# untitled.net
KiCad netlist of a schematic drawn in EAGLE
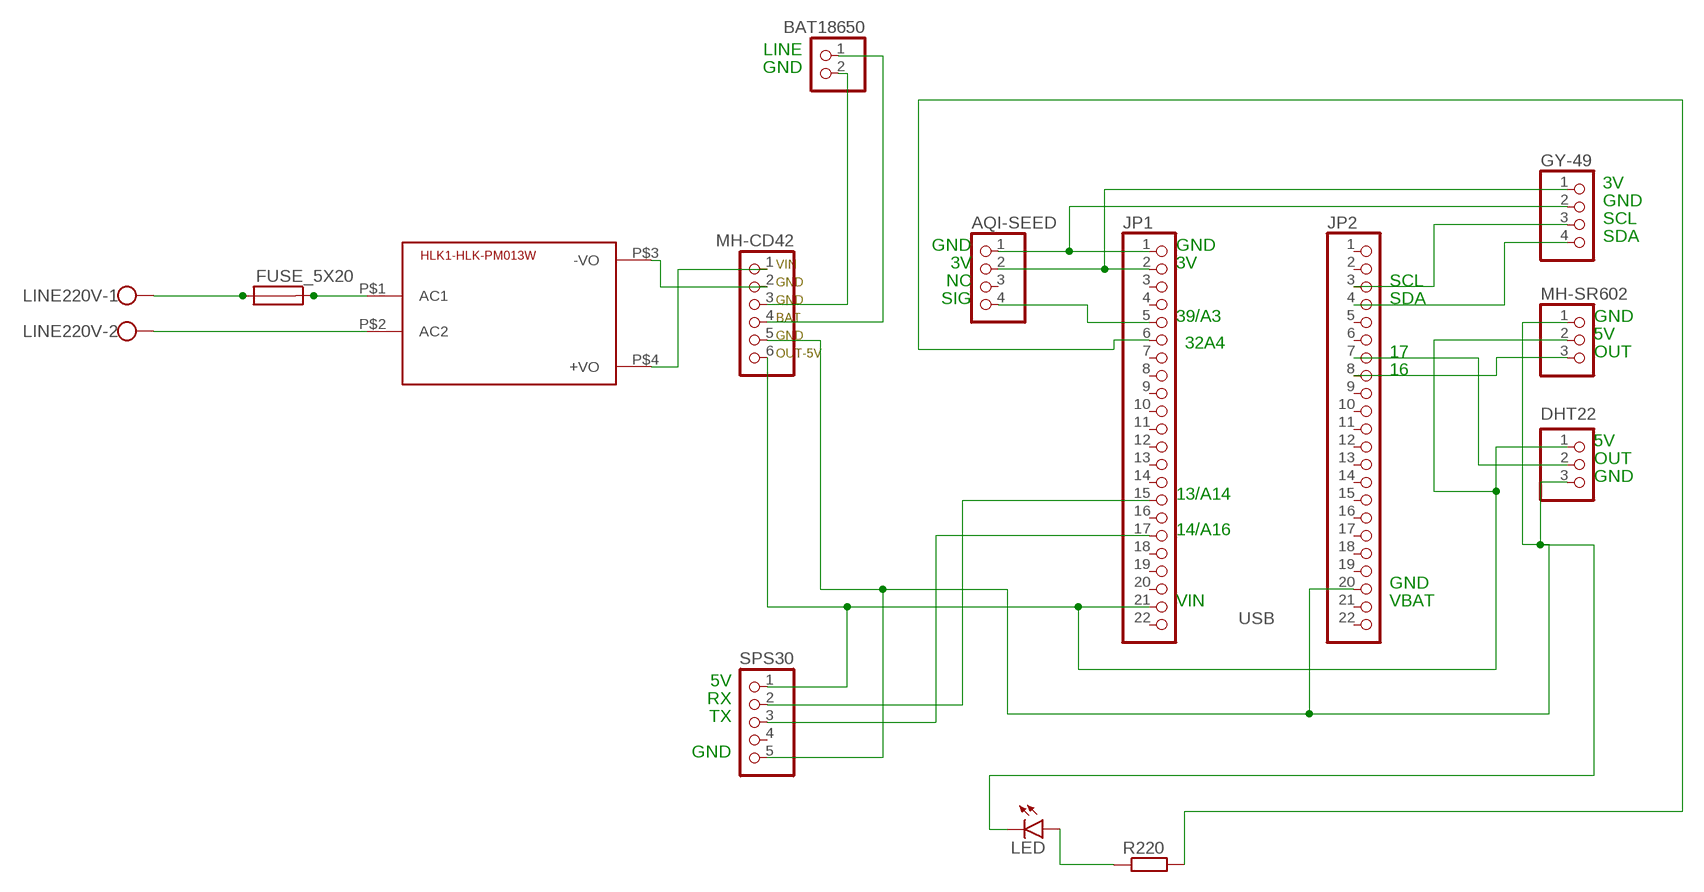
[diagram p0: schematic, sheet 1]

(export (version "E")
  (design (tool "Eeschema 10.0.6"))
  (components
    (comp (ref "AQI-SEED")
      (value "PINHD-1X4")
      (footprint "eagle-import:1X04")
      (libsource (lib "eagle-import") (part "PINHD-1X4"))
    )
    (comp (ref "BAT18650")
      (value "PINHD-1X2")
      (footprint "eagle-import:1X02")
      (libsource (lib "eagle-import") (part "PINHD-1X2"))
    )
    (comp (ref "FUSE_5X20")
      (value "FH_5X20")
      (footprint "eagle-import:FH_5X20")
      (libsource (lib "eagle-import") (part "FH_5X20"))
    )
    (comp (ref "GY-49")
      (value "PINHD-1X4")
      (footprint "eagle-import:1X04")
      (libsource (lib "eagle-import") (part "PINHD-1X4"))
    )
    (comp (ref "HLK1-HLK-PM013W")
      (value "HLK-PM013W")
      (footprint "eagle-import:HLK-PM01")
      (libsource (lib "eagle-import") (part "HLK-PM013W"))
    )
    (comp (ref "JP1")
      (value "PINHD-1X22")
      (footprint "eagle-import:1X22")
      (libsource (lib "eagle-import") (part "PINHD-1X22"))
    )
    (comp (ref "JP2")
      (value "PINHD-1X22")
      (footprint "eagle-import:1X22")
      (libsource (lib "eagle-import") (part "PINHD-1X22"))
    )
    (comp (ref "JP6")
      (value "DHT22")
      (footprint "eagle-import:1X03")
      (libsource (lib "eagle-import") (part "PINHD-1X3"))
    )
    (comp (ref "LED")
      (value "LED3MM")
      (footprint "eagle-import:LED3MM")
      (libsource (lib "eagle-import") (part "LED3MM"))
    )
    (comp (ref "LINE220V")
      (value "W237-102")
      (footprint "eagle-import:W237-102")
      (fields (field (name "MPN") "237-102"))
      (libsource (lib "eagle-import") (part "W237-102"))
    )
    (comp (ref "MH-CD42")
      (value "PINHD-1X6")
      (footprint "eagle-import:1X06")
      (fields (field (name "SPICEPREFIX") "X"))
      (libsource (lib "eagle-import") (part "PINHD-1X6"))
    )
    (comp (ref "MH-SR602")
      (value "PINHD-1X3")
      (footprint "eagle-import:1X03")
      (libsource (lib "eagle-import") (part "PINHD-1X3"))
    )
    (comp (ref "R220")
      (value "R-EU_0204/5")
      (footprint "eagle-import:0204_5")
      (libsource (lib "eagle-import") (part "R-EU_0204/5"))
    )
    (comp (ref "SPS30")
      (value "PINHD-1X5")
      (footprint "eagle-import:1X05")
      (libsource (lib "eagle-import") (part "PINHD-1X5"))
    )
  )
  (nets
    (net (code "1") (name "Net-(AQI-SEED-Pad1)") (class "Default")
      (node (ref "AQI-SEED") (pin "1") (pinfunction "1_1") (pintype "passive"))
      (node (ref "GY-49") (pin "2") (pinfunction "2_2") (pintype "passive"))
      (node (ref "JP1") (pin "1") (pinfunction "1_1") (pintype "passive"))
    )
    (net (code "2") (name "Net-(AQI-SEED-Pad2)") (class "Default")
      (node (ref "AQI-SEED") (pin "2") (pinfunction "2_2") (pintype "passive"))
      (node (ref "GY-49") (pin "1") (pinfunction "1_1") (pintype "passive"))
      (node (ref "JP1") (pin "2") (pinfunction "2_2") (pintype "passive"))
    )
    (net (code "3") (name "Net-(AQI-SEED-Pad4)") (class "Default")
      (node (ref "AQI-SEED") (pin "4") (pinfunction "4_4") (pintype "passive"))
      (node (ref "JP1") (pin "5") (pinfunction "5_5") (pintype "passive"))
    )
    (net (code "4") (name "Net-(BAT18650-Pad1)") (class "Default")
      (node (ref "BAT18650") (pin "1") (pinfunction "1_1") (pintype "passive"))
      (node (ref "MH-CD42") (pin "4") (pinfunction "4_4") (pintype "passive"))
    )
    (net (code "5") (name "Net-(BAT18650-Pad2)") (class "Default")
      (node (ref "BAT18650") (pin "2") (pinfunction "2_2") (pintype "passive"))
      (node (ref "MH-CD42") (pin "3") (pinfunction "3_3") (pintype "passive"))
    )
    (net (code "6") (name "Net-(GY-49-Pad3)") (class "Default")
      (node (ref "GY-49") (pin "3") (pinfunction "3_3") (pintype "passive"))
      (node (ref "JP2") (pin "3") (pinfunction "3_3") (pintype "passive"))
    )
    (net (code "7") (name "Net-(GY-49-Pad4)") (class "Default")
      (node (ref "GY-49") (pin "4") (pinfunction "4_4") (pintype "passive"))
      (node (ref "JP2") (pin "4") (pinfunction "4_4") (pintype "passive"))
    )
    (net (code "8") (name "Net-(HLK1-HLK-PM013W-+VO)") (class "Default")
      (node (ref "HLK1-HLK-PM013W") (pin "P$4") (pinfunction "+VO_P$4") (pintype "bidirectional"))
      (node (ref "MH-CD42") (pin "1") (pinfunction "1_1") (pintype "passive"))
    )
    (net (code "9") (name "Net-(HLK1-HLK-PM013W--VO)") (class "Default")
      (node (ref "HLK1-HLK-PM013W") (pin "P$3") (pinfunction "-VO_P$3") (pintype "bidirectional"))
      (node (ref "MH-CD42") (pin "2") (pinfunction "2_2") (pintype "passive"))
    )
    (net (code "10") (name "Net-(HLK1-HLK-PM013W-AC1)") (class "Default")
      (node (ref "FUSE_5X20") (pin "2A") (pinfunction "2A_2A") (pintype "passive"))
      (node (ref "FUSE_5X20") (pin "2B") (pinfunction "2B_2B") (pintype "passive"))
      (node (ref "HLK1-HLK-PM013W") (pin "P$1") (pinfunction "AC1_P$1") (pintype "bidirectional"))
    )
    (net (code "11") (name "Net-(HLK1-HLK-PM013W-AC2)") (class "Default")
      (node (ref "HLK1-HLK-PM013W") (pin "P$2") (pinfunction "AC2_P$2") (pintype "bidirectional"))
      (node (ref "LINE220V") (pin "2") (pinfunction "KL_2") (pintype "passive"))
    )
    (net (code "12") (name "Net-(JP1-Pad6)") (class "Default")
      (node (ref "JP1") (pin "6") (pinfunction "6_6") (pintype "passive"))
      (node (ref "R220") (pin "2") (pinfunction "2_2") (pintype "passive"))
    )
    (net (code "13") (name "Net-(JP1-Pad15)") (class "Default")
      (node (ref "JP1") (pin "15") (pinfunction "15_15") (pintype "passive"))
      (node (ref "SPS30") (pin "2") (pinfunction "2_2") (pintype "passive"))
    )
    (net (code "14") (name "Net-(JP1-Pad17)") (class "Default")
      (node (ref "JP1") (pin "17") (pinfunction "17_17") (pintype "passive"))
      (node (ref "SPS30") (pin "3") (pinfunction "3_3") (pintype "passive"))
    )
    (net (code "15") (name "Net-(JP1-Pad21)") (class "Default")
      (node (ref "JP1") (pin "21") (pinfunction "21_21") (pintype "passive"))
      (node (ref "JP6") (pin "1") (pinfunction "1_1") (pintype "passive"))
      (node (ref "MH-CD42") (pin "6") (pinfunction "6_6") (pintype "passive"))
      (node (ref "MH-SR602") (pin "2") (pinfunction "2_2") (pintype "passive"))
      (node (ref "SPS30") (pin "1") (pinfunction "1_1") (pintype "passive"))
    )
    (net (code "16") (name "Net-(JP2-Pad7)") (class "Default")
      (node (ref "JP2") (pin "7") (pinfunction "7_7") (pintype "passive"))
      (node (ref "JP6") (pin "2") (pinfunction "2_2") (pintype "passive"))
    )
    (net (code "17") (name "Net-(JP2-Pad8)") (class "Default")
      (node (ref "JP2") (pin "8") (pinfunction "8_8") (pintype "passive"))
      (node (ref "MH-SR602") (pin "3") (pinfunction "3_3") (pintype "passive"))
    )
    (net (code "18") (name "Net-(LED-C)") (class "Default")
      (node (ref "JP2") (pin "20") (pinfunction "20_20") (pintype "passive"))
      (node (ref "JP6") (pin "3") (pinfunction "3_3") (pintype "passive"))
      (node (ref "LED") (pin "K") (pinfunction "C_K") (pintype "passive"))
      (node (ref "MH-CD42") (pin "5") (pinfunction "5_5") (pintype "passive"))
      (node (ref "MH-SR602") (pin "1") (pinfunction "1_1") (pintype "passive"))
      (node (ref "SPS30") (pin "5") (pinfunction "5_5") (pintype "passive"))
    )
    (net (code "19") (name "Net-(LED-PadA)") (class "Default")
      (node (ref "LED") (pin "A") (pinfunction "A_A") (pintype "passive"))
      (node (ref "R220") (pin "1") (pinfunction "1_1") (pintype "passive"))
    )
    (net (code "20") (name "Net-(LINE220VA-KL)") (class "Default")
      (node (ref "FUSE_5X20") (pin "1A") (pinfunction "1A_1A") (pintype "passive"))
      (node (ref "FUSE_5X20") (pin "1B") (pinfunction "1B_1B") (pintype "passive"))
      (node (ref "LINE220V") (pin "1") (pinfunction "KL_1") (pintype "passive"))
    )
    (net (code "21") (name "unconnected-(AQI-SEED-Pad3)") (class "Default")
      (node (ref "AQI-SEED") (pin "3") (pinfunction "3_3") (pintype "passive"))
    )
    (net (code "22") (name "unconnected-(JP1-Pad3)") (class "Default")
      (node (ref "JP1") (pin "3") (pinfunction "3_3") (pintype "passive"))
    )
    (net (code "23") (name "unconnected-(JP1-Pad4)") (class "Default")
      (node (ref "JP1") (pin "4") (pinfunction "4_4") (pintype "passive"))
    )
    (net (code "24") (name "unconnected-(JP1-Pad7)") (class "Default")
      (node (ref "JP1") (pin "7") (pinfunction "7_7") (pintype "passive"))
    )
    (net (code "25") (name "unconnected-(JP1-Pad8)") (class "Default")
      (node (ref "JP1") (pin "8") (pinfunction "8_8") (pintype "passive"))
    )
    (net (code "26") (name "unconnected-(JP1-Pad9)") (class "Default")
      (node (ref "JP1") (pin "9") (pinfunction "9_9") (pintype "passive"))
    )
    (net (code "27") (name "unconnected-(JP1-Pad10)") (class "Default")
      (node (ref "JP1") (pin "10") (pinfunction "10_10") (pintype "passive"))
    )
    (net (code "28") (name "unconnected-(JP1-Pad11)") (class "Default")
      (node (ref "JP1") (pin "11") (pinfunction "11_11") (pintype "passive"))
    )
    (net (code "29") (name "unconnected-(JP1-Pad12)") (class "Default")
      (node (ref "JP1") (pin "12") (pinfunction "12_12") (pintype "passive"))
    )
    (net (code "30") (name "unconnected-(JP1-Pad13)") (class "Default")
      (node (ref "JP1") (pin "13") (pinfunction "13_13") (pintype "passive"))
    )
    (net (code "31") (name "unconnected-(JP1-Pad14)") (class "Default")
      (node (ref "JP1") (pin "14") (pinfunction "14_14") (pintype "passive"))
    )
    (net (code "32") (name "unconnected-(JP1-Pad16)") (class "Default")
      (node (ref "JP1") (pin "16") (pinfunction "16_16") (pintype "passive"))
    )
    (net (code "33") (name "unconnected-(JP1-Pad18)") (class "Default")
      (node (ref "JP1") (pin "18") (pinfunction "18_18") (pintype "passive"))
    )
    (net (code "34") (name "unconnected-(JP1-Pad19)") (class "Default")
      (node (ref "JP1") (pin "19") (pinfunction "19_19") (pintype "passive"))
    )
    (net (code "35") (name "unconnected-(JP1-Pad20)") (class "Default")
      (node (ref "JP1") (pin "20") (pinfunction "20_20") (pintype "passive"))
    )
    (net (code "36") (name "unconnected-(JP1-Pad22)") (class "Default")
      (node (ref "JP1") (pin "22") (pinfunction "22_22") (pintype "passive"))
    )
    (net (code "37") (name "unconnected-(JP2-Pad1)") (class "Default")
      (node (ref "JP2") (pin "1") (pinfunction "1_1") (pintype "passive"))
    )
    (net (code "38") (name "unconnected-(JP2-Pad2)") (class "Default")
      (node (ref "JP2") (pin "2") (pinfunction "2_2") (pintype "passive"))
    )
    (net (code "39") (name "unconnected-(JP2-Pad5)") (class "Default")
      (node (ref "JP2") (pin "5") (pinfunction "5_5") (pintype "passive"))
    )
    (net (code "40") (name "unconnected-(JP2-Pad6)") (class "Default")
      (node (ref "JP2") (pin "6") (pinfunction "6_6") (pintype "passive"))
    )
    (net (code "41") (name "unconnected-(JP2-Pad9)") (class "Default")
      (node (ref "JP2") (pin "9") (pinfunction "9_9") (pintype "passive"))
    )
    (net (code "42") (name "unconnected-(JP2-Pad10)") (class "Default")
      (node (ref "JP2") (pin "10") (pinfunction "10_10") (pintype "passive"))
    )
    (net (code "43") (name "unconnected-(JP2-Pad11)") (class "Default")
      (node (ref "JP2") (pin "11") (pinfunction "11_11") (pintype "passive"))
    )
    (net (code "44") (name "unconnected-(JP2-Pad12)") (class "Default")
      (node (ref "JP2") (pin "12") (pinfunction "12_12") (pintype "passive"))
    )
    (net (code "45") (name "unconnected-(JP2-Pad13)") (class "Default")
      (node (ref "JP2") (pin "13") (pinfunction "13_13") (pintype "passive"))
    )
    (net (code "46") (name "unconnected-(JP2-Pad14)") (class "Default")
      (node (ref "JP2") (pin "14") (pinfunction "14_14") (pintype "passive"))
    )
    (net (code "47") (name "unconnected-(JP2-Pad15)") (class "Default")
      (node (ref "JP2") (pin "15") (pinfunction "15_15") (pintype "passive"))
    )
    (net (code "48") (name "unconnected-(JP2-Pad16)") (class "Default")
      (node (ref "JP2") (pin "16") (pinfunction "16_16") (pintype "passive"))
    )
    (net (code "49") (name "unconnected-(JP2-Pad17)") (class "Default")
      (node (ref "JP2") (pin "17") (pinfunction "17_17") (pintype "passive"))
    )
    (net (code "50") (name "unconnected-(JP2-Pad18)") (class "Default")
      (node (ref "JP2") (pin "18") (pinfunction "18_18") (pintype "passive"))
    )
    (net (code "51") (name "unconnected-(JP2-Pad19)") (class "Default")
      (node (ref "JP2") (pin "19") (pinfunction "19_19") (pintype "passive"))
    )
    (net (code "52") (name "unconnected-(JP2-Pad21)") (class "Default")
      (node (ref "JP2") (pin "21") (pinfunction "21_21") (pintype "passive"))
    )
    (net (code "53") (name "unconnected-(JP2-Pad22)") (class "Default")
      (node (ref "JP2") (pin "22") (pinfunction "22_22") (pintype "passive"))
    )
    (net (code "54") (name "unconnected-(SPS30-Pad4)") (class "Default")
      (node (ref "SPS30") (pin "4") (pinfunction "4_4") (pintype "passive"))
    )
  )
)
